# ATtiny85_and_DRV8830_Combo_--_v05.net
KiCad netlist of a schematic drawn in EAGLE
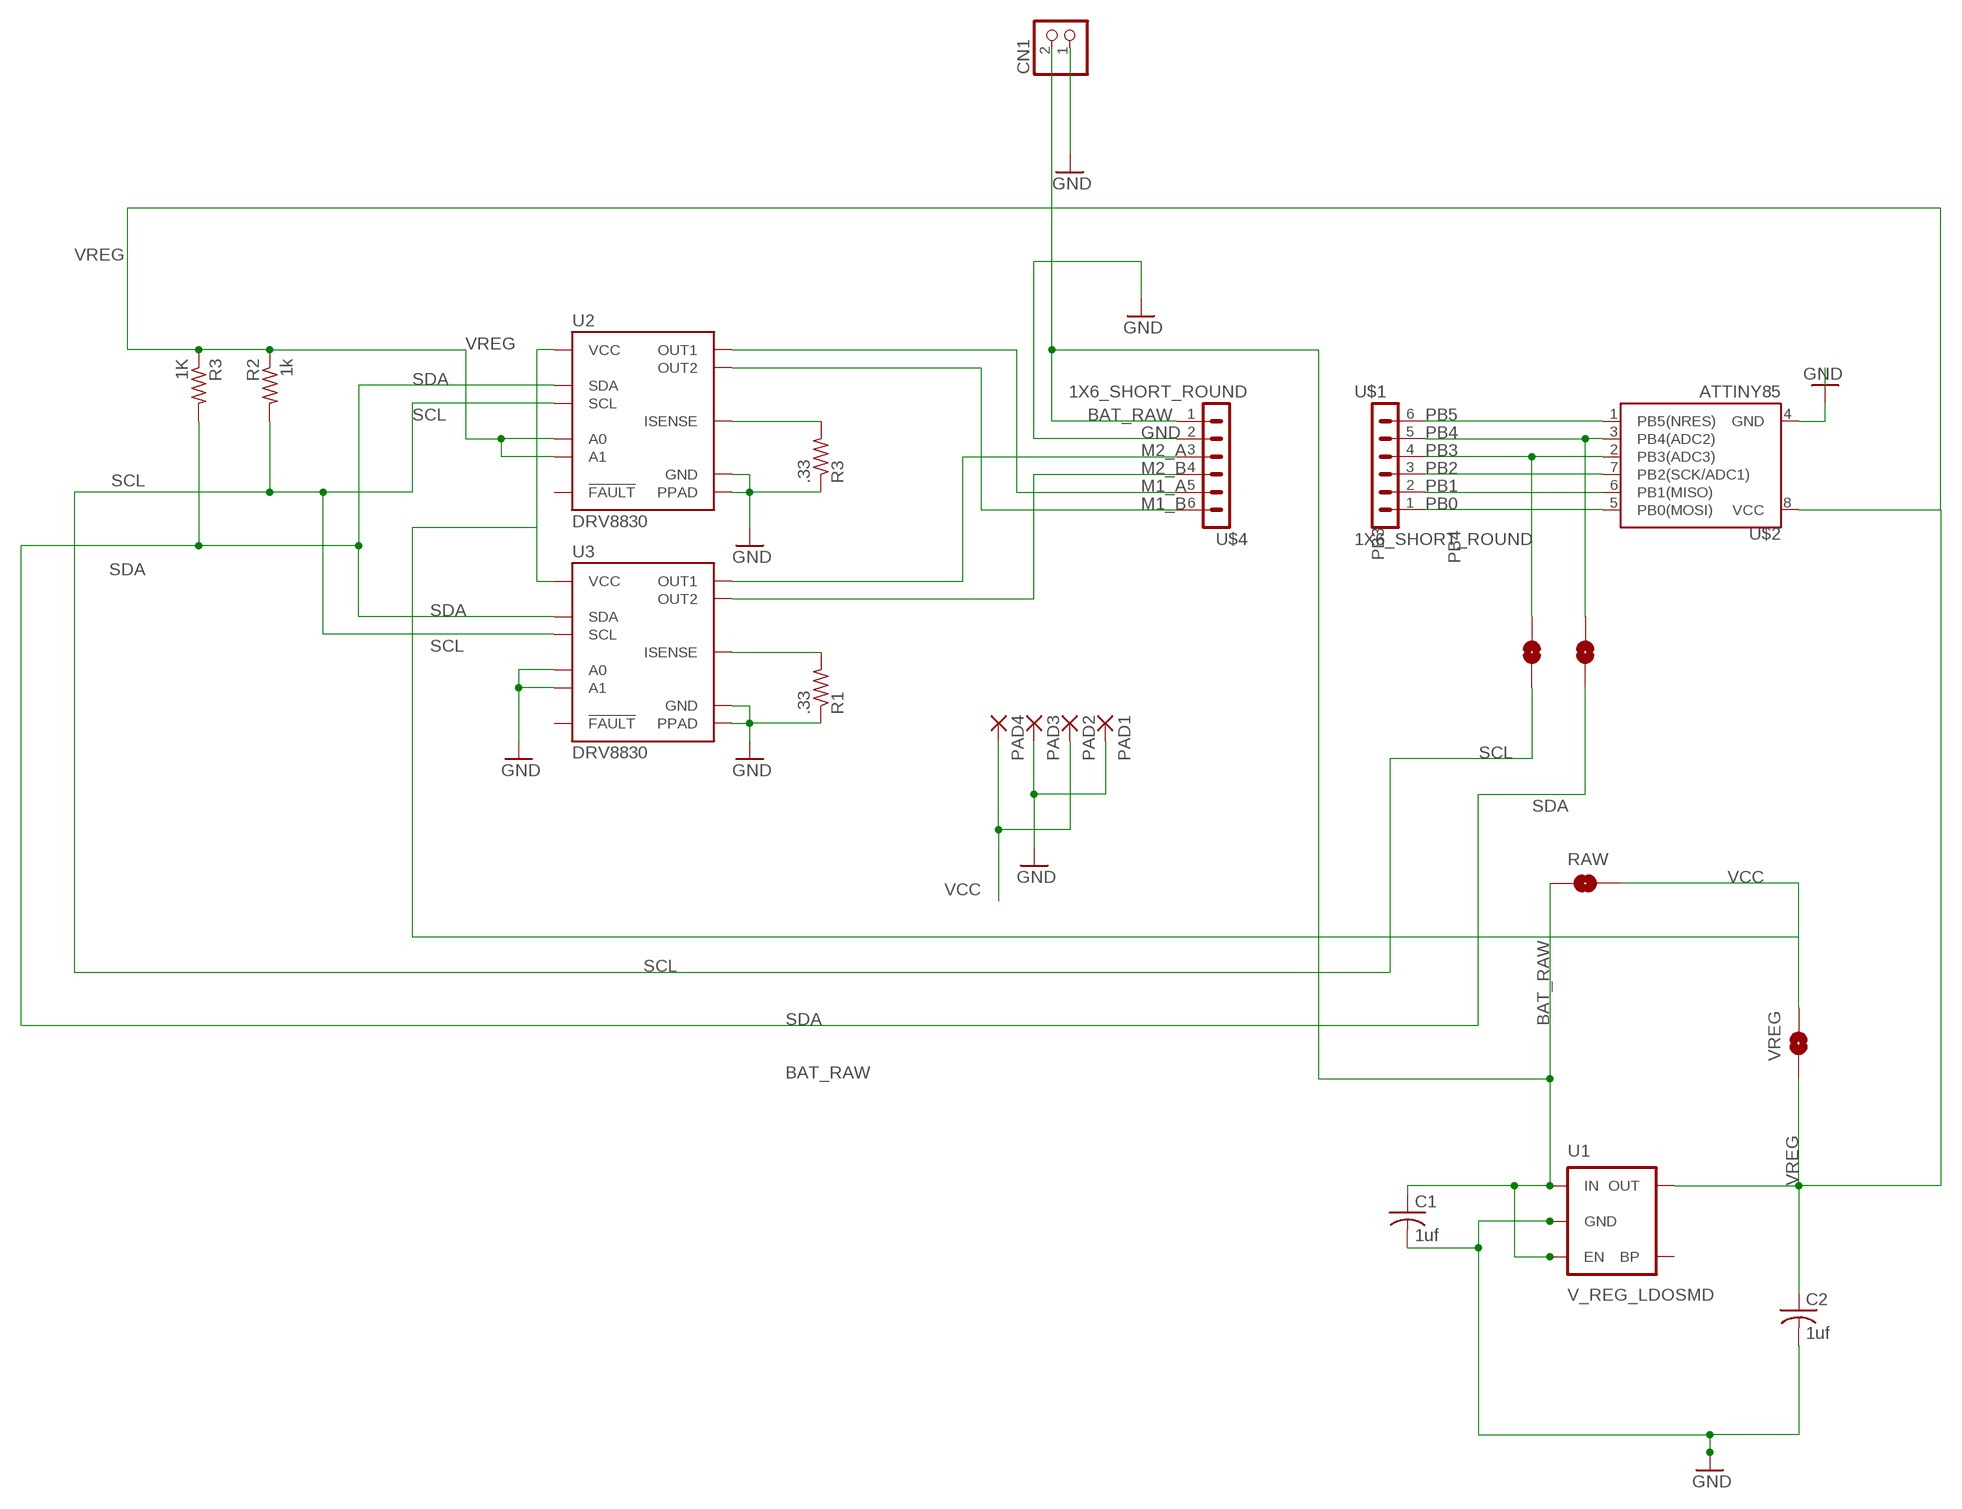
[diagram p0: schematic, sheet 1]

(export (version "E")
  (design (tool "Eeschema 10.0.6"))
  (components
    (comp (ref "1K")
      (value "R3")
      (footprint "eagle-import:R0402")
      (libsource (lib "eagle-import") (part "R-US_R0402"))
    )
    (comp (ref "C1")
      (value "1uf")
      (footprint "eagle-import:C0402")
      (libsource (lib "eagle-import") (part "C-USC0402"))
    )
    (comp (ref "C2")
      (value "1uf")
      (footprint "eagle-import:C0402")
      (libsource (lib "eagle-import") (part "C-USC0402"))
    )
    (comp (ref "CN1")
      (value "JST_2PIN-THM")
      (footprint "eagle-import:JST-PH-2-THM")
      (libsource (lib "eagle-import") (part "JST_2PIN-THM"))
    )
    (comp (ref "PAD1")
      (value "SMD2")
      (footprint "eagle-import:SMD1,27-2,54")
      (libsource (lib "eagle-import") (part "SMD2"))
    )
    (comp (ref "PAD2")
      (value "SMD2")
      (footprint "eagle-import:SMD1,27-2,54")
      (libsource (lib "eagle-import") (part "SMD2"))
    )
    (comp (ref "PAD3")
      (value "SMD2")
      (footprint "eagle-import:SMD1,27-2,54")
      (libsource (lib "eagle-import") (part "SMD2"))
    )
    (comp (ref "PAD4")
      (value "SMD2")
      (footprint "eagle-import:SMD1,27-2,54")
      (libsource (lib "eagle-import") (part "SMD2"))
    )
    (comp (ref "R1")
      (value ".33")
      (footprint "eagle-import:R0402")
      (libsource (lib "eagle-import") (part "R-US_R0402"))
    )
    (comp (ref "R2")
      (value "1k")
      (footprint "eagle-import:R0402")
      (libsource (lib "eagle-import") (part "R-US_R0402"))
    )
    (comp (ref "R3")
      (value ".33")
      (footprint "eagle-import:R0402")
      (libsource (lib "eagle-import") (part "R-US_R0402"))
    )
    (comp (ref "RAW")
      (value "SOLDERJUMPERNO")
      (footprint "eagle-import:SJ_2S-NO")
      (libsource (lib "eagle-import") (part "SOLDERJUMPERNO"))
    )
    (comp (ref "SJ6")
      (value "SOLDERJUMPERNO")
      (footprint "eagle-import:SJ_2S-NO")
      (libsource (lib "eagle-import") (part "SOLDERJUMPERNO"))
    )
    (comp (ref "SJ7")
      (value "SOLDERJUMPERNO")
      (footprint "eagle-import:SJ_2S-NO")
      (libsource (lib "eagle-import") (part "SOLDERJUMPERNO"))
    )
    (comp (ref "U$1")
      (value "1X6_SHORT_ROUND")
      (footprint "eagle-import:1X6_SHORT_ROUND")
      (libsource (lib "eagle-import") (part "1X6_SHORT_ROUND"))
    )
    (comp (ref "U$2")
      (value "ATTINY85")
      (footprint "eagle-import:SO08-EIAJ")
      (libsource (lib "eagle-import") (part "ATTINY45"))
    )
    (comp (ref "U$4")
      (value "1X6_SHORT_ROUND")
      (footprint "eagle-import:1X6_SHORT_ROUND")
      (libsource (lib "eagle-import") (part "1X6_SHORT_ROUND"))
    )
    (comp (ref "U1")
      (value "V_REG_LDOSMD")
      (footprint "eagle-import:SOT23-5")
      (libsource (lib "eagle-import") (part "V_REG_LDOSMD"))
    )
    (comp (ref "U2")
      (value "DRV8830")
      (footprint "eagle-import:MSOP-10-GNDPAD")
      (libsource (lib "eagle-import") (part "DRV8830"))
    )
    (comp (ref "U3")
      (value "DRV8830")
      (footprint "eagle-import:MSOP-10-GNDPAD")
      (libsource (lib "eagle-import") (part "DRV8830"))
    )
    (comp (ref "VREG")
      (value "SOLDERJUMPERNO")
      (footprint "eagle-import:SJ_2S-NO")
      (libsource (lib "eagle-import") (part "SOLDERJUMPERNO"))
    )
  )
  (nets
    (net (code "1") (name "/BAT_RAW") (class "Default")
      (node (ref "C1") (pin "1") (pinfunction "1_1") (pintype "passive"))
      (node (ref "CN1") (pin "2") (pinfunction "1_2") (pintype "passive"))
      (node (ref "RAW") (pin "1") (pinfunction "1_1") (pintype "passive"))
      (node (ref "U$4") (pin "1") (pinfunction "1_1") (pintype "passive"))
      (node (ref "U1") (pin "1") (pinfunction "IN_1") (pintype "input"))
      (node (ref "U1") (pin "3") (pinfunction "EN_3") (pintype "input"))
    )
    (net (code "2") (name "/M1_A") (class "Default")
      (node (ref "U$4") (pin "5") (pinfunction "5_5") (pintype "passive"))
      (node (ref "U2") (pin "3") (pinfunction "OUT1_3") (pintype "power_in"))
    )
    (net (code "3") (name "/M1_B") (class "Default")
      (node (ref "U$4") (pin "6") (pinfunction "6_6") (pintype "passive"))
      (node (ref "U2") (pin "1") (pinfunction "OUT2_1") (pintype "power_in"))
    )
    (net (code "4") (name "/M2_A") (class "Default")
      (node (ref "U$4") (pin "3") (pinfunction "3_3") (pintype "passive"))
      (node (ref "U3") (pin "3") (pinfunction "OUT1_3") (pintype "power_in"))
    )
    (net (code "5") (name "/M2_B") (class "Default")
      (node (ref "U$4") (pin "4") (pinfunction "4_4") (pintype "passive"))
      (node (ref "U3") (pin "1") (pinfunction "OUT2_1") (pintype "power_in"))
    )
    (net (code "6") (name "/PB0") (class "Default")
      (node (ref "U$1") (pin "1") (pinfunction "1_1") (pintype "passive"))
      (node (ref "U$2") (pin "5") (pinfunction "PB0(MOSI)_5") (pintype "bidirectional"))
    )
    (net (code "7") (name "/PB1") (class "Default")
      (node (ref "U$1") (pin "2") (pinfunction "2_2") (pintype "passive"))
      (node (ref "U$2") (pin "6") (pinfunction "PB1(MISO)_6") (pintype "bidirectional"))
    )
    (net (code "8") (name "/PB2") (class "Default")
      (node (ref "U$1") (pin "3") (pinfunction "3_3") (pintype "passive"))
      (node (ref "U$2") (pin "7") (pinfunction "PB2(SCK/ADC1)_7") (pintype "bidirectional"))
    )
    (net (code "9") (name "/PB3") (class "Default")
      (node (ref "SJ7") (pin "2") (pinfunction "2_2") (pintype "passive"))
      (node (ref "U$1") (pin "4") (pinfunction "4_4") (pintype "passive"))
      (node (ref "U$2") (pin "2") (pinfunction "PB3(ADC3)_2") (pintype "bidirectional"))
    )
    (net (code "10") (name "/PB4") (class "Default")
      (node (ref "SJ6") (pin "2") (pinfunction "2_2") (pintype "passive"))
      (node (ref "U$1") (pin "5") (pinfunction "5_5") (pintype "passive"))
      (node (ref "U$2") (pin "3") (pinfunction "PB4(ADC2)_3") (pintype "bidirectional"))
    )
    (net (code "11") (name "/PB5") (class "Default")
      (node (ref "U$1") (pin "6") (pinfunction "6_6") (pintype "passive"))
      (node (ref "U$2") (pin "1") (pinfunction "PB5(NRES)_1") (pintype "bidirectional"))
    )
    (net (code "12") (name "/SCL") (class "Default")
      (node (ref "R2") (pin "2") (pinfunction "2_2") (pintype "passive"))
      (node (ref "SJ7") (pin "1") (pinfunction "1_1") (pintype "passive"))
      (node (ref "U2") (pin "10") (pinfunction "SCL_10") (pintype "input"))
      (node (ref "U3") (pin "10") (pinfunction "SCL_10") (pintype "input"))
    )
    (net (code "13") (name "/SDA") (class "Default")
      (node (ref "1K") (pin "2") (pinfunction "2_2") (pintype "passive"))
      (node (ref "SJ6") (pin "1") (pinfunction "1_1") (pintype "passive"))
      (node (ref "U2") (pin "9") (pinfunction "SDA_9") (pintype "bidirectional"))
      (node (ref "U3") (pin "9") (pinfunction "SDA_9") (pintype "bidirectional"))
    )
    (net (code "14") (name "/VCC") (class "Default")
      (node (ref "PAD2") (pin "1") (pinfunction "P_1") (pintype "passive"))
      (node (ref "PAD4") (pin "1") (pinfunction "P_1") (pintype "passive"))
      (node (ref "RAW") (pin "2") (pinfunction "2_2") (pintype "passive"))
      (node (ref "U2") (pin "4") (pinfunction "VCC_4") (pintype "power_in"))
      (node (ref "U3") (pin "4") (pinfunction "VCC_4") (pintype "power_in"))
      (node (ref "VREG") (pin "2") (pinfunction "2_2") (pintype "passive"))
    )
    (net (code "15") (name "/VREG") (class "Default")
      (node (ref "1K") (pin "1") (pinfunction "1_1") (pintype "passive"))
      (node (ref "C2") (pin "1") (pinfunction "1_1") (pintype "passive"))
      (node (ref "R2") (pin "1") (pinfunction "1_1") (pintype "passive"))
      (node (ref "U$2") (pin "8") (pinfunction "VCC_8") (pintype "bidirectional"))
      (node (ref "U1") (pin "5") (pinfunction "OUT_5") (pintype "passive"))
      (node (ref "U2") (pin "7") (pinfunction "A0_7") (pintype "input"))
      (node (ref "U2") (pin "8") (pinfunction "A1_8") (pintype "input"))
      (node (ref "VREG") (pin "1") (pinfunction "1_1") (pintype "passive"))
    )
    (net (code "16") (name "GND") (class "Default")
      (node (ref "C1") (pin "2") (pinfunction "2_2") (pintype "passive"))
      (node (ref "C2") (pin "2") (pinfunction "2_2") (pintype "passive"))
      (node (ref "CN1") (pin "1") (pinfunction "2_1") (pintype "passive"))
      (node (ref "PAD1") (pin "1") (pinfunction "P_1") (pintype "passive"))
      (node (ref "PAD3") (pin "1") (pinfunction "P_1") (pintype "passive"))
      (node (ref "R1") (pin "1") (pinfunction "1_1") (pintype "passive"))
      (node (ref "R3") (pin "1") (pinfunction "1_1") (pintype "passive"))
      (node (ref "U$2") (pin "4") (pinfunction "GND_4") (pintype "bidirectional"))
      (node (ref "U$4") (pin "2") (pinfunction "2_2") (pintype "passive"))
      (node (ref "U1") (pin "2") (pinfunction "GND_2") (pintype "input"))
      (node (ref "U2") (pin "5") (pinfunction "GND_5") (pintype "power_in"))
      (node (ref "U2") (pin "GND") (pinfunction "PPAD_GND") (pintype "power_in"))
      (node (ref "U3") (pin "5") (pinfunction "GND_5") (pintype "power_in"))
      (node (ref "U3") (pin "7") (pinfunction "A0_7") (pintype "input"))
      (node (ref "U3") (pin "8") (pinfunction "A1_8") (pintype "input"))
      (node (ref "U3") (pin "GND") (pinfunction "PPAD_GND") (pintype "power_in"))
    )
    (net (code "17") (name "Net-(U2-ISENSE)") (class "Default")
      (node (ref "R3") (pin "2") (pinfunction "2_2") (pintype "passive"))
      (node (ref "U2") (pin "2") (pinfunction "ISENSE_2") (pintype "bidirectional"))
    )
    (net (code "18") (name "Net-(U3-ISENSE)") (class "Default")
      (node (ref "R1") (pin "2") (pinfunction "2_2") (pintype "passive"))
      (node (ref "U3") (pin "2") (pinfunction "ISENSE_2") (pintype "bidirectional"))
    )
    (net (code "19") (name "unconnected-(U1-BP-Pad4)") (class "Default")
      (node (ref "U1") (pin "4") (pinfunction "BP_4") (pintype "input"))
    )
    (net (code "20") (name "unconnected-(U2-~{FAULT}-Pad6)") (class "Default")
      (node (ref "U2") (pin "6") (pinfunction "~{FAULT}_6") (pintype "output"))
    )
    (net (code "21") (name "unconnected-(U3-~{FAULT}-Pad6)") (class "Default")
      (node (ref "U3") (pin "6") (pinfunction "~{FAULT}_6") (pintype "output"))
    )
  )
)
